# Controller.net
KiCad netlist of a schematic drawn in EAGLE
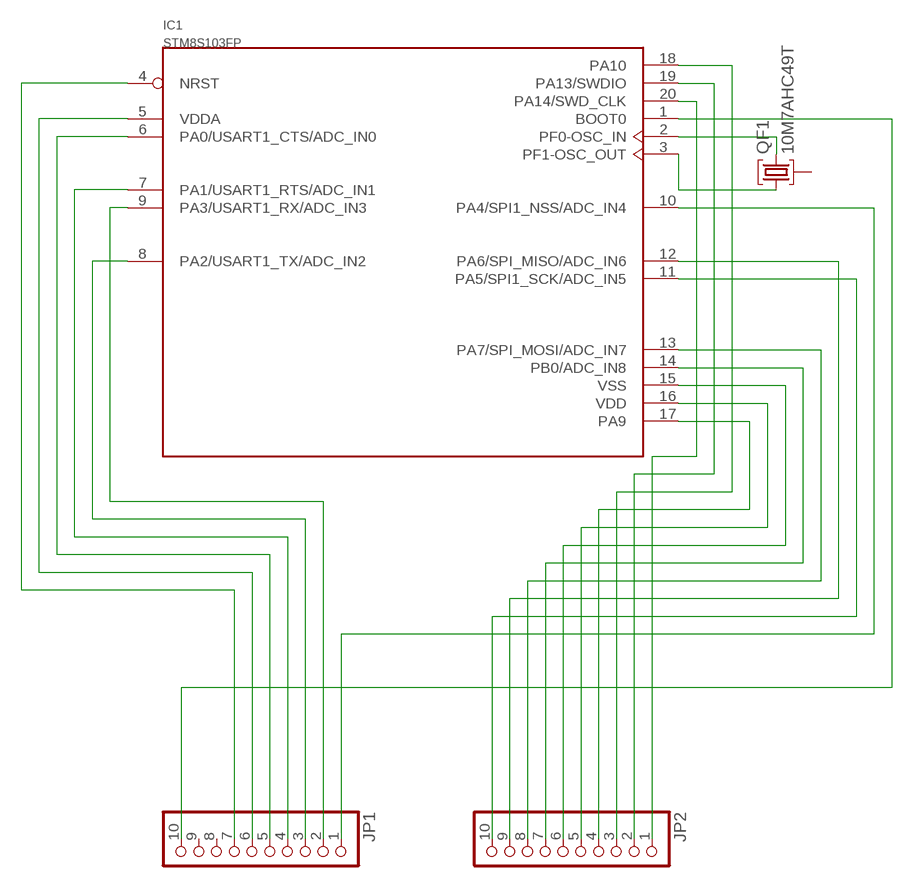
[diagram p0: schematic, sheet 1]

(export (version "E")
  (design (tool "Eeschema 10.0.6"))
  (components
    (comp (ref "IC1")
      (value "STM8S103FP")
      (footprint "eagle-import:TSSOP20")
      (libsource (lib "eagle-import") (part "STM8S103FP"))
    )
    (comp (ref "JP1")
      (value "PINHD-1X10")
      (footprint "eagle-import:1X10")
      (libsource (lib "eagle-import") (part "PINHD-1X10"))
    )
    (comp (ref "JP2")
      (value "PINHD-1X10")
      (footprint "eagle-import:1X10")
      (libsource (lib "eagle-import") (part "PINHD-1X10"))
    )
    (comp (ref "QF1")
      (value "10M7AHC49T")
      (footprint "eagle-import:HC49U")
      (libsource (lib "eagle-import") (part "10MAHC49T7"))
    )
  )
  (nets
    (net (code "1") (name "Net-(IC1-BOOT0)") (class "Default")
      (node (ref "IC1") (pin "1") (pinfunction "BOOT0_1") (pintype "bidirectional"))
      (node (ref "JP1") (pin "10") (pinfunction "10_10") (pintype "passive"))
    )
    (net (code "2") (name "Net-(IC1-NRST)") (class "Default")
      (node (ref "IC1") (pin "4") (pinfunction "NRST_4") (pintype "bidirectional"))
      (node (ref "JP1") (pin "7") (pinfunction "7_7") (pintype "passive"))
    )
    (net (code "3") (name "Net-(IC1-PA0{slash}USART1_CTS{slash}ADC_IN0)") (class "Default")
      (node (ref "IC1") (pin "6") (pinfunction "PA0/USART1_CTS/ADC_IN0_6") (pintype "bidirectional"))
      (node (ref "JP1") (pin "5") (pinfunction "5_5") (pintype "passive"))
    )
    (net (code "4") (name "Net-(IC1-PA1{slash}USART1_RTS{slash}ADC_IN1)") (class "Default")
      (node (ref "IC1") (pin "7") (pinfunction "PA1/USART1_RTS/ADC_IN1_7") (pintype "bidirectional"))
      (node (ref "JP1") (pin "4") (pinfunction "4_4") (pintype "passive"))
    )
    (net (code "5") (name "Net-(IC1-PA2{slash}USART1_TX{slash}ADC_IN2)") (class "Default")
      (node (ref "IC1") (pin "8") (pinfunction "PA2/USART1_TX/ADC_IN2_8") (pintype "bidirectional"))
      (node (ref "JP1") (pin "3") (pinfunction "3_3") (pintype "passive"))
    )
    (net (code "6") (name "Net-(IC1-PA3{slash}USART1_RX{slash}ADC_IN3)") (class "Default")
      (node (ref "IC1") (pin "9") (pinfunction "PA3/USART1_RX/ADC_IN3_9") (pintype "bidirectional"))
      (node (ref "JP1") (pin "2") (pinfunction "2_2") (pintype "passive"))
    )
    (net (code "7") (name "Net-(IC1-PA4{slash}SPI1_NSS{slash}ADC_IN4)") (class "Default")
      (node (ref "IC1") (pin "10") (pinfunction "PA4/SPI1_NSS/ADC_IN4_10") (pintype "bidirectional"))
      (node (ref "JP1") (pin "1") (pinfunction "1_1") (pintype "passive"))
    )
    (net (code "8") (name "Net-(IC1-PA5{slash}SPI1_SCK{slash}ADC_IN5)") (class "Default")
      (node (ref "IC1") (pin "11") (pinfunction "PA5/SPI1_SCK/ADC_IN5_11") (pintype "bidirectional"))
      (node (ref "JP2") (pin "10") (pinfunction "10_10") (pintype "passive"))
    )
    (net (code "9") (name "Net-(IC1-PA6{slash}SPI_MISO{slash}ADC_IN6)") (class "Default")
      (node (ref "IC1") (pin "12") (pinfunction "PA6/SPI_MISO/ADC_IN6_12") (pintype "bidirectional"))
      (node (ref "JP2") (pin "9") (pinfunction "9_9") (pintype "passive"))
    )
    (net (code "10") (name "Net-(IC1-PA7{slash}SPI_MOSI{slash}ADC_IN7)") (class "Default")
      (node (ref "IC1") (pin "13") (pinfunction "PA7/SPI_MOSI/ADC_IN7_13") (pintype "bidirectional"))
      (node (ref "JP2") (pin "8") (pinfunction "8_8") (pintype "passive"))
    )
    (net (code "11") (name "Net-(IC1-PA9)") (class "Default")
      (node (ref "IC1") (pin "17") (pinfunction "PA9_17") (pintype "bidirectional"))
      (node (ref "JP2") (pin "4") (pinfunction "4_4") (pintype "passive"))
    )
    (net (code "12") (name "Net-(IC1-PA10)") (class "Default")
      (node (ref "IC1") (pin "18") (pinfunction "PA10_18") (pintype "bidirectional"))
      (node (ref "JP2") (pin "3") (pinfunction "3_3") (pintype "passive"))
    )
    (net (code "13") (name "Net-(IC1-PA13{slash}SWDIO)") (class "Default")
      (node (ref "IC1") (pin "19") (pinfunction "PA13/SWDIO_19") (pintype "bidirectional"))
      (node (ref "JP2") (pin "2") (pinfunction "2_2") (pintype "passive"))
    )
    (net (code "14") (name "Net-(IC1-PA14{slash}SWD_CLK)") (class "Default")
      (node (ref "IC1") (pin "20") (pinfunction "PA14/SWD_CLK_20") (pintype "bidirectional"))
      (node (ref "JP2") (pin "1") (pinfunction "1_1") (pintype "passive"))
    )
    (net (code "15") (name "Net-(IC1-PB0{slash}ADC_IN8)") (class "Default")
      (node (ref "IC1") (pin "14") (pinfunction "PB0/ADC_IN8_14") (pintype "bidirectional"))
      (node (ref "JP2") (pin "7") (pinfunction "7_7") (pintype "passive"))
    )
    (net (code "16") (name "Net-(IC1-PF0-OSC_IN)") (class "Default")
      (node (ref "IC1") (pin "2") (pinfunction "PF0-OSC_IN_2") (pintype "bidirectional"))
      (node (ref "QF1") (pin "3") (pinfunction "3_3") (pintype "passive"))
    )
    (net (code "17") (name "Net-(IC1-PF1-OSC_OUT)") (class "Default")
      (node (ref "IC1") (pin "3") (pinfunction "PF1-OSC_OUT_3") (pintype "bidirectional"))
      (node (ref "QF1") (pin "1") (pinfunction "1_1") (pintype "passive"))
    )
    (net (code "18") (name "Net-(IC1-VDD)") (class "Default")
      (node (ref "IC1") (pin "16") (pinfunction "VDD_16") (pintype "power_in"))
      (node (ref "JP2") (pin "5") (pinfunction "5_5") (pintype "passive"))
    )
    (net (code "19") (name "Net-(IC1-VDDA)") (class "Default")
      (node (ref "IC1") (pin "5") (pinfunction "VDDA_5") (pintype "power_in"))
      (node (ref "JP1") (pin "6") (pinfunction "6_6") (pintype "passive"))
    )
    (net (code "20") (name "Net-(IC1-VSS)") (class "Default")
      (node (ref "IC1") (pin "15") (pinfunction "VSS_15") (pintype "power_in"))
      (node (ref "JP2") (pin "6") (pinfunction "6_6") (pintype "passive"))
    )
    (net (code "21") (name "unconnected-(JP1-Pad8)") (class "Default")
      (node (ref "JP1") (pin "8") (pinfunction "8_8") (pintype "passive"))
    )
    (net (code "22") (name "unconnected-(JP1-Pad9)") (class "Default")
      (node (ref "JP1") (pin "9") (pinfunction "9_9") (pintype "passive"))
    )
    (net (code "23") (name "unconnected-(QF1-Pad2)") (class "Default")
      (node (ref "QF1") (pin "2") (pinfunction "2_2") (pintype "passive"))
    )
  )
)
